# RoboFly.net
KiCad netlist of a schematic drawn in Altium Designer
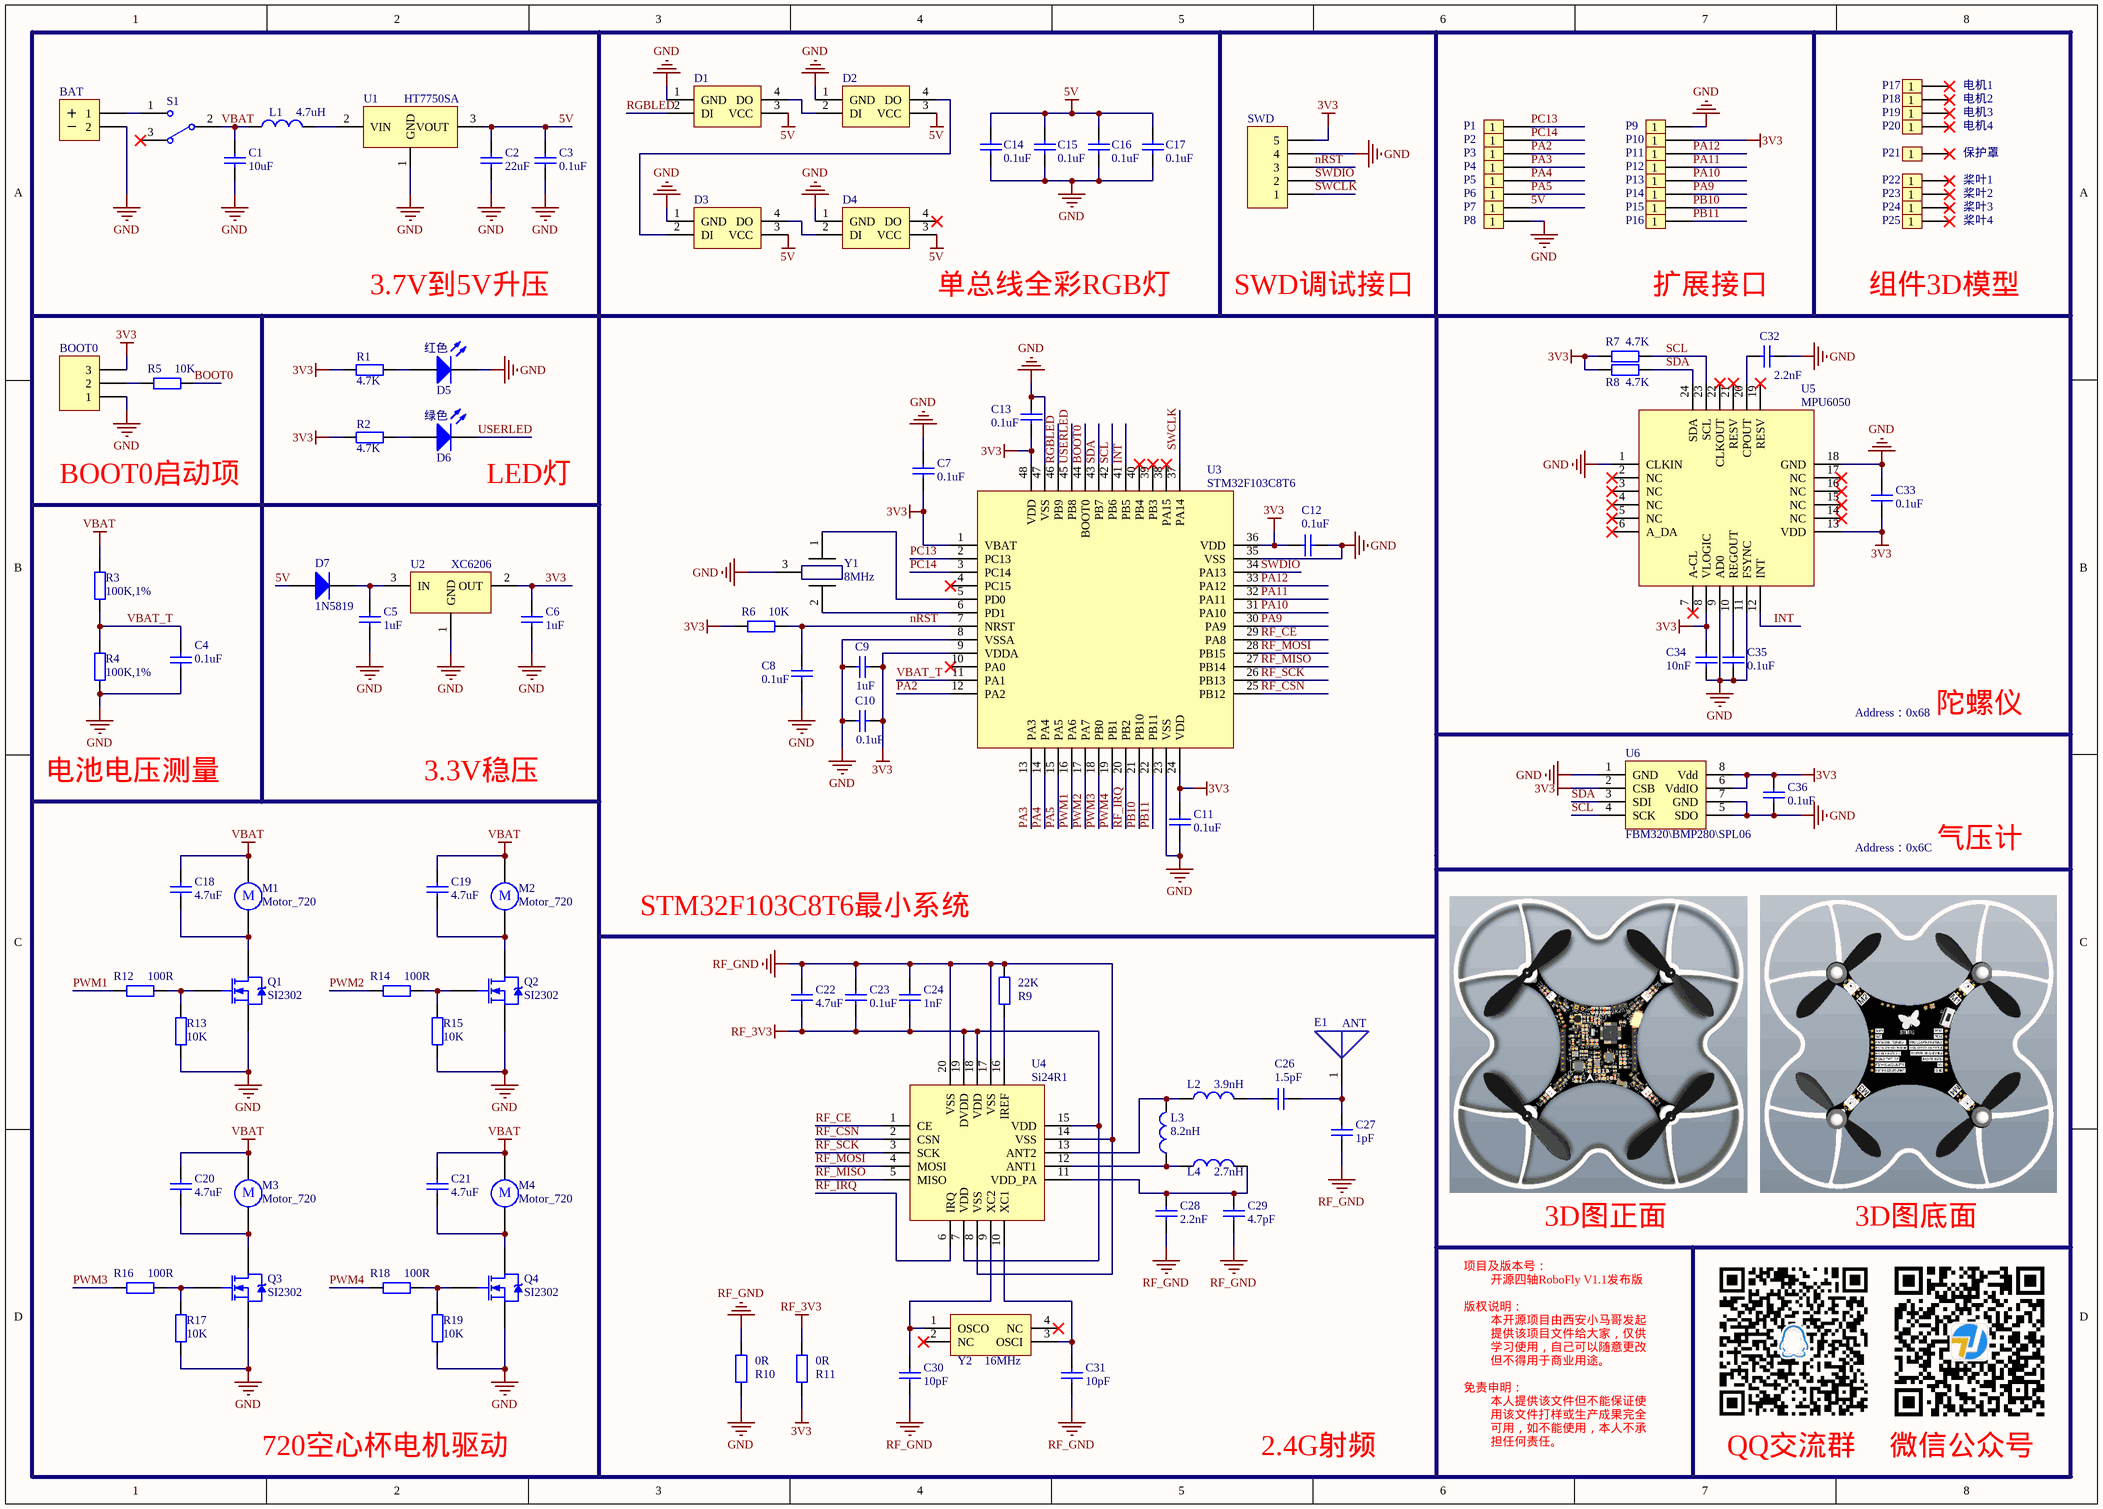
[diagram p0: RoboFly.SchDoc]

(export (version "E")
  (design (tool "Eeschema 10.0.6"))
  (components
    (comp (ref "BAT")
      (value "BAT")
      (footprint "BAT")
      (description "Header, 2-Pin")
      (fields (field (name "PUBLISHER") "mazhongwei"))
      (libsource (lib "RoboFly") (part "BAT"))
    )
    (comp (ref "BOOT0")
      (value "BOOT")
      (footprint "HEADER1X3")
      (description "Header, 3-Pin")
      (fields (field (name "PUBLISHER") "Altium Limited"))
      (libsource (lib "RoboFly") (part "Header 3"))
    )
    (comp (ref "C1")
      (value "10uF")
      (footprint "C_0603")
      (fields (field (name "Comment") "C_0603") (field (name "PUBLISHER") "Altium Limited"))
      (libsource (lib "RoboFly") (part "C_0603"))
    )
    (comp (ref "C2")
      (value "22uF")
      (footprint "C_0603")
      (fields (field (name "Comment") "C_0603") (field (name "PUBLISHER") "Altium Limited"))
      (libsource (lib "RoboFly") (part "C_0603"))
    )
    (comp (ref "C3")
      (value "0.1uF")
      (footprint "C_0603")
      (fields (field (name "Comment") "C_0603") (field (name "PUBLISHER") "Altium Limited"))
      (libsource (lib "RoboFly") (part "C_0603"))
    )
    (comp (ref "C4")
      (value "0.1uF")
      (footprint "C_0603")
      (fields (field (name "Comment") "C_0603") (field (name "PUBLISHER") "Altium Limited"))
      (libsource (lib "RoboFly") (part "C_0603"))
    )
    (comp (ref "C5")
      (value "1uF")
      (footprint "C_0603")
      (fields (field (name "Comment") "C_0603") (field (name "PUBLISHER") "Altium Limited"))
      (libsource (lib "RoboFly") (part "C_0603"))
    )
    (comp (ref "C6")
      (value "1uF")
      (footprint "C_0603")
      (fields (field (name "Comment") "C_0603") (field (name "PUBLISHER") "Altium Limited"))
      (libsource (lib "RoboFly") (part "C_0603"))
    )
    (comp (ref "C7")
      (value "0.1uF")
      (footprint "C_0603")
      (fields (field (name "Comment") "C_0603") (field (name "PUBLISHER") "Altium Limited"))
      (libsource (lib "RoboFly") (part "C_0603"))
    )
    (comp (ref "C8")
      (value "0.1uF")
      (footprint "C_0603")
      (fields (field (name "Comment") "C_0603") (field (name "PUBLISHER") "Altium Limited"))
      (libsource (lib "RoboFly") (part "C_0603"))
    )
    (comp (ref "C9")
      (value "1uF")
      (footprint "C_0603")
      (fields (field (name "Comment") "C_0603") (field (name "PUBLISHER") "Altium Limited"))
      (libsource (lib "RoboFly") (part "C_0603"))
    )
    (comp (ref "C10")
      (value "0.1uF")
      (footprint "C_0603")
      (fields (field (name "Comment") "C_0603") (field (name "PUBLISHER") "Altium Limited"))
      (libsource (lib "RoboFly") (part "C_0603"))
    )
    (comp (ref "C11")
      (value "0.1uF")
      (footprint "C_0603")
      (fields (field (name "Comment") "C_0603") (field (name "PUBLISHER") "Altium Limited"))
      (libsource (lib "RoboFly") (part "C_0603"))
    )
    (comp (ref "C12")
      (value "0.1uF")
      (footprint "C_0603")
      (fields (field (name "Comment") "C_0603") (field (name "PUBLISHER") "Altium Limited"))
      (libsource (lib "RoboFly") (part "C_0603"))
    )
    (comp (ref "C13")
      (value "0.1uF")
      (footprint "C_0603")
      (fields (field (name "Comment") "C_0603") (field (name "PUBLISHER") "Altium Limited"))
      (libsource (lib "RoboFly") (part "C_0603"))
    )
    (comp (ref "C14")
      (value "0.1uF")
      (footprint "C_0603")
      (fields (field (name "Comment") "C_0603") (field (name "PUBLISHER") "Altium Limited"))
      (libsource (lib "RoboFly") (part "C_0603"))
    )
    (comp (ref "C15")
      (value "0.1uF")
      (footprint "C_0603")
      (fields (field (name "Comment") "C_0603") (field (name "PUBLISHER") "Altium Limited"))
      (libsource (lib "RoboFly") (part "C_0603"))
    )
    (comp (ref "C16")
      (value "0.1uF")
      (footprint "C_0603")
      (fields (field (name "Comment") "C_0603") (field (name "PUBLISHER") "Altium Limited"))
      (libsource (lib "RoboFly") (part "C_0603"))
    )
    (comp (ref "C17")
      (value "0.1uF")
      (footprint "C_0603")
      (fields (field (name "Comment") "C_0603") (field (name "PUBLISHER") "Altium Limited"))
      (libsource (lib "RoboFly") (part "C_0603"))
    )
    (comp (ref "C18")
      (value "4.7uF")
      (footprint "C_0603")
      (fields (field (name "Comment") "C_0603") (field (name "PUBLISHER") "Altium Limited"))
      (libsource (lib "RoboFly") (part "C_0603"))
    )
    (comp (ref "C19")
      (value "4.7uF")
      (footprint "C_0603")
      (fields (field (name "Comment") "C_0603") (field (name "PUBLISHER") "Altium Limited"))
      (libsource (lib "RoboFly") (part "C_0603"))
    )
    (comp (ref "C20")
      (value "4.7uF")
      (footprint "C_0603")
      (fields (field (name "Comment") "C_0603") (field (name "PUBLISHER") "Altium Limited"))
      (libsource (lib "RoboFly") (part "C_0603"))
    )
    (comp (ref "C21")
      (value "4.7uF")
      (footprint "C_0603")
      (fields (field (name "Comment") "C_0603") (field (name "PUBLISHER") "Altium Limited"))
      (libsource (lib "RoboFly") (part "C_0603"))
    )
    (comp (ref "C22")
      (value "4.7uF")
      (footprint "C_0603")
      (fields (field (name "Comment") "C_0603") (field (name "PUBLISHER") "Altium Limited"))
      (libsource (lib "RoboFly") (part "C_0603"))
    )
    (comp (ref "C23")
      (value "0.1uF")
      (footprint "C_0603")
      (fields (field (name "Comment") "C_0603") (field (name "PUBLISHER") "Altium Limited"))
      (libsource (lib "RoboFly") (part "C_0603"))
    )
    (comp (ref "C24")
      (value "1nF")
      (footprint "C_0603")
      (fields (field (name "Comment") "C_0603") (field (name "PUBLISHER") "Altium Limited"))
      (libsource (lib "RoboFly") (part "C_0603"))
    )
    (comp (ref "C26")
      (value "1.5pF")
      (footprint "C_0603")
      (fields (field (name "Comment") "C_0603") (field (name "PUBLISHER") "Altium Limited"))
      (libsource (lib "RoboFly") (part "C_0603"))
    )
    (comp (ref "C27")
      (value "1pF")
      (footprint "C_0603")
      (fields (field (name "Comment") "C_0603") (field (name "PUBLISHER") "Altium Limited"))
      (libsource (lib "RoboFly") (part "C_0603"))
    )
    (comp (ref "C28")
      (value "2.2nF")
      (footprint "C_0603")
      (fields (field (name "Comment") "C_0603") (field (name "PUBLISHER") "Altium Limited"))
      (libsource (lib "RoboFly") (part "C_0603"))
    )
    (comp (ref "C29")
      (value "4.7pF")
      (footprint "C_0603")
      (fields (field (name "Comment") "C_0603") (field (name "PUBLISHER") "Altium Limited"))
      (libsource (lib "RoboFly") (part "C_0603"))
    )
    (comp (ref "C30")
      (value "10pF")
      (footprint "C_0603")
      (fields (field (name "Comment") "C_0603") (field (name "PUBLISHER") "Altium Limited"))
      (libsource (lib "RoboFly") (part "C_0603"))
    )
    (comp (ref "C31")
      (value "10pF")
      (footprint "C_0603")
      (fields (field (name "Comment") "C_0603") (field (name "PUBLISHER") "Altium Limited"))
      (libsource (lib "RoboFly") (part "C_0603"))
    )
    (comp (ref "C32")
      (value "2.2nF")
      (footprint "C_0603")
      (fields (field (name "Comment") "C_0603") (field (name "PUBLISHER") "Altium Limited"))
      (libsource (lib "RoboFly") (part "C_0603"))
    )
    (comp (ref "C33")
      (value "0.1uF")
      (footprint "C_0603")
      (fields (field (name "Comment") "C_0603") (field (name "PUBLISHER") "Altium Limited"))
      (libsource (lib "RoboFly") (part "C_0603"))
    )
    (comp (ref "C34")
      (value "10nF")
      (footprint "C_0603")
      (fields (field (name "Comment") "C_0603") (field (name "PUBLISHER") "Altium Limited"))
      (libsource (lib "RoboFly") (part "C_0603"))
    )
    (comp (ref "C35")
      (value "0.1uF")
      (footprint "C_0603")
      (fields (field (name "Comment") "C_0603") (field (name "PUBLISHER") "Altium Limited"))
      (libsource (lib "RoboFly") (part "C_0603"))
    )
    (comp (ref "C36")
      (value "0.1uF")
      (footprint "C_0603")
      (fields (field (name "Comment") "C_0603") (field (name "PUBLISHER") "Altium Limited"))
      (libsource (lib "RoboFly") (part "C_0603"))
    )
    (comp (ref "D1")
      (value "P923D")
      (footprint "RGB_LED_5050")
      (fields (field (name "PUBLISHER") "mazhongwei"))
      (libsource (lib "RoboFly") (part "P923D"))
    )
    (comp (ref "D2")
      (value "P923D")
      (footprint "RGB_LED_5050")
      (fields (field (name "PUBLISHER") "mazhongwei"))
      (libsource (lib "RoboFly") (part "P923D"))
    )
    (comp (ref "D3")
      (value "P923D")
      (footprint "RGB_LED_5050")
      (fields (field (name "PUBLISHER") "mazhongwei"))
      (libsource (lib "RoboFly") (part "P923D"))
    )
    (comp (ref "D4")
      (value "P923D")
      (footprint "RGB_LED_5050")
      (fields (field (name "PUBLISHER") "mazhongwei"))
      (libsource (lib "RoboFly") (part "P923D"))
    )
    (comp (ref "D5")
      (value "红色")
      (footprint "LED-0603")
      (description "发光二极管")
      (fields (field (name "PUBLISHER") "Altium Limited"))
      (libsource (lib "RoboFly") (part "LED 0603"))
    )
    (comp (ref "D6")
      (value "绿色")
      (footprint "LED-0603")
      (description "发光二极管")
      (fields (field (name "PUBLISHER") "Altium Limited"))
      (libsource (lib "RoboFly") (part "LED 0603"))
    )
    (comp (ref "D7")
      (value "1N5819")
      (footprint "SOD-123")
      (description "Default Diode")
      (fields (field (name "PUBLISHER") "mazhongwei"))
      (libsource (lib "RoboFly") (part "Diode"))
    )
    (comp (ref "E1")
      (value "ANT")
      (footprint "ANT")
      (fields (field (name "PUBLISHER") "mazhongwei"))
      (libsource (lib "RoboFly") (part "ANT"))
    )
    (comp (ref "L1")
      (value "4.7uH")
      (footprint "L_1210")
      (description "电感")
      (fields (field (name "Comment") "Inductor") (field (name "PUBLISHER") "Altium Limited"))
      (libsource (lib "RoboFly") (part "Inductor"))
    )
    (comp (ref "L2")
      (value "3.9nH")
      (footprint "L_0603")
      (description "电感")
      (fields (field (name "Comment") "Inductor") (field (name "PUBLISHER") "Altium Limited"))
      (libsource (lib "RoboFly") (part "Inductor_1"))
    )
    (comp (ref "L3")
      (value "8.2nH")
      (footprint "L_0603")
      (description "电感")
      (fields (field (name "Comment") "Inductor") (field (name "PUBLISHER") "Altium Limited"))
      (libsource (lib "RoboFly") (part "Inductor_1"))
    )
    (comp (ref "L4")
      (value "2.7nH")
      (footprint "L_0603")
      (description "电感")
      (fields (field (name "Comment") "Inductor") (field (name "PUBLISHER") "Altium Limited"))
      (libsource (lib "RoboFly") (part "Inductor_1"))
    )
    (comp (ref "M1")
      (value "Motor_720")
      (footprint "MOTOR")
      (description "Motor, General Kind")
      (fields (field (name "PUBLISHER") "mazhongwei"))
      (libsource (lib "RoboFly") (part "Motor_720"))
    )
    (comp (ref "M2")
      (value "Motor_720")
      (footprint "MOTOR")
      (description "Motor, General Kind")
      (fields (field (name "PUBLISHER") "mazhongwei"))
      (libsource (lib "RoboFly") (part "Motor_720"))
    )
    (comp (ref "M3")
      (value "Motor_720")
      (footprint "MOTOR")
      (description "Motor, General Kind")
      (fields (field (name "PUBLISHER") "mazhongwei"))
      (libsource (lib "RoboFly") (part "Motor_720"))
    )
    (comp (ref "M4")
      (value "Motor_720")
      (footprint "MOTOR")
      (description "Motor, General Kind")
      (fields (field (name "PUBLISHER") "mazhongwei"))
      (libsource (lib "RoboFly") (part "Motor_720"))
    )
    (comp (ref "P1")
      (value "Header 1")
      (footprint "HEADER1")
      (fields (field (name "PUBLISHER") "Altium Limited"))
      (libsource (lib "RoboFly") (part "Header 1"))
    )
    (comp (ref "P2")
      (value "Header 1")
      (footprint "HEADER1")
      (fields (field (name "PUBLISHER") "Altium Limited"))
      (libsource (lib "RoboFly") (part "Header 1"))
    )
    (comp (ref "P3")
      (value "Header 1")
      (footprint "HEADER1")
      (fields (field (name "PUBLISHER") "Altium Limited"))
      (libsource (lib "RoboFly") (part "Header 1"))
    )
    (comp (ref "P4")
      (value "Header 1")
      (footprint "HEADER1")
      (fields (field (name "PUBLISHER") "Altium Limited"))
      (libsource (lib "RoboFly") (part "Header 1"))
    )
    (comp (ref "P5")
      (value "Header 1")
      (footprint "HEADER1")
      (fields (field (name "PUBLISHER") "Altium Limited"))
      (libsource (lib "RoboFly") (part "Header 1"))
    )
    (comp (ref "P6")
      (value "Header 1")
      (footprint "HEADER1")
      (fields (field (name "PUBLISHER") "Altium Limited"))
      (libsource (lib "RoboFly") (part "Header 1"))
    )
    (comp (ref "P7")
      (value "Header 1")
      (footprint "HEADER1")
      (fields (field (name "PUBLISHER") "Altium Limited"))
      (libsource (lib "RoboFly") (part "Header 1"))
    )
    (comp (ref "P8")
      (value "Header 1")
      (footprint "HEADER1")
      (fields (field (name "PUBLISHER") "Altium Limited"))
      (libsource (lib "RoboFly") (part "Header 1"))
    )
    (comp (ref "P9")
      (value "Header 1")
      (footprint "HEADER1")
      (fields (field (name "PUBLISHER") "Altium Limited"))
      (libsource (lib "RoboFly") (part "Header 1"))
    )
    (comp (ref "P10")
      (value "Header 1")
      (footprint "HEADER1")
      (fields (field (name "PUBLISHER") "Altium Limited"))
      (libsource (lib "RoboFly") (part "Header 1"))
    )
    (comp (ref "P11")
      (value "Header 1")
      (footprint "HEADER1")
      (fields (field (name "PUBLISHER") "Altium Limited"))
      (libsource (lib "RoboFly") (part "Header 1"))
    )
    (comp (ref "P12")
      (value "Header 1")
      (footprint "HEADER1")
      (fields (field (name "PUBLISHER") "Altium Limited"))
      (libsource (lib "RoboFly") (part "Header 1"))
    )
    (comp (ref "P13")
      (value "Header 1")
      (footprint "HEADER1")
      (fields (field (name "PUBLISHER") "Altium Limited"))
      (libsource (lib "RoboFly") (part "Header 1"))
    )
    (comp (ref "P14")
      (value "Header 1")
      (footprint "HEADER1")
      (fields (field (name "PUBLISHER") "Altium Limited"))
      (libsource (lib "RoboFly") (part "Header 1"))
    )
    (comp (ref "P15")
      (value "Header 1")
      (footprint "HEADER1")
      (fields (field (name "PUBLISHER") "Altium Limited"))
      (libsource (lib "RoboFly") (part "Header 1"))
    )
    (comp (ref "P16")
      (value "Header 1")
      (footprint "HEADER1")
      (fields (field (name "PUBLISHER") "Altium Limited"))
      (libsource (lib "RoboFly") (part "Header 1"))
    )
    (comp (ref "P17")
      (value "Header 1")
      (footprint "720Motor")
      (fields (field (name "PUBLISHER") "Altium Limited"))
      (libsource (lib "RoboFly") (part "Header 1"))
    )
    (comp (ref "P18")
      (value "Header 1")
      (footprint "720Motor")
      (fields (field (name "PUBLISHER") "Altium Limited"))
      (libsource (lib "RoboFly") (part "Header 1"))
    )
    (comp (ref "P19")
      (value "Header 1")
      (footprint "720Motor")
      (fields (field (name "PUBLISHER") "Altium Limited"))
      (libsource (lib "RoboFly") (part "Header 1"))
    )
    (comp (ref "P20")
      (value "Header 1")
      (footprint "720Motor")
      (fields (field (name "PUBLISHER") "Altium Limited"))
      (libsource (lib "RoboFly") (part "Header 1"))
    )
    (comp (ref "P21")
      (value "Header 1")
      (footprint "PROTECT_COVER")
      (fields (field (name "PUBLISHER") "Altium Limited"))
      (libsource (lib "RoboFly") (part "Header 1"))
    )
    (comp (ref "P22")
      (value "Header 1")
      (footprint "BLADEB")
      (fields (field (name "PUBLISHER") "Altium Limited"))
      (libsource (lib "RoboFly") (part "Header 1"))
    )
    (comp (ref "P23")
      (value "Header 1")
      (footprint "BLADEA")
      (fields (field (name "PUBLISHER") "Altium Limited"))
      (libsource (lib "RoboFly") (part "Header 1"))
    )
    (comp (ref "P24")
      (value "Header 1")
      (footprint "BLADEB")
      (fields (field (name "PUBLISHER") "Altium Limited"))
      (libsource (lib "RoboFly") (part "Header 1"))
    )
    (comp (ref "P25")
      (value "Header 1")
      (footprint "BLADEA")
      (fields (field (name "PUBLISHER") "Altium Limited"))
      (libsource (lib "RoboFly") (part "Header 1"))
    )
    (comp (ref "Q1")
      (value "SI2302")
      (footprint "SOT-23(SOT-23-3)")
      (description "N-Channel Power MOSFET")
      (fields (field (name "PUBLISHER") "mazhongwei"))
      (libsource (lib "RoboFly") (part "SI2302"))
    )
    (comp (ref "Q2")
      (value "SI2302")
      (footprint "SOT-23(SOT-23-3)")
      (description "N-Channel Power MOSFET")
      (fields (field (name "PUBLISHER") "mazhongwei"))
      (libsource (lib "RoboFly") (part "SI2302"))
    )
    (comp (ref "Q3")
      (value "SI2302")
      (footprint "SOT-23(SOT-23-3)")
      (description "N-Channel Power MOSFET")
      (fields (field (name "PUBLISHER") "mazhongwei"))
      (libsource (lib "RoboFly") (part "SI2302"))
    )
    (comp (ref "Q4")
      (value "SI2302")
      (footprint "SOT-23(SOT-23-3)")
      (description "N-Channel Power MOSFET")
      (fields (field (name "PUBLISHER") "mazhongwei"))
      (libsource (lib "RoboFly") (part "SI2302"))
    )
    (comp (ref "R1")
      (value "4.7K")
      (footprint "R_0603")
      (fields (field (name "Comment") "R_0603") (field (name "PUBLISHER") "Altium Limited"))
      (libsource (lib "") (part "R_0603_1"))
    )
    (comp (ref "R2")
      (value "4.7K")
      (footprint "R_0603")
      (fields (field (name "Comment") "R_0603") (field (name "PUBLISHER") "Altium Limited"))
      (libsource (lib "") (part "R_0603_1"))
    )
    (comp (ref "R3")
      (value "100K,1%")
      (footprint "R_0603")
      (fields (field (name "Comment") "R_0603") (field (name "PUBLISHER") "Altium Limited"))
      (libsource (lib "RoboFly") (part "R_0603"))
    )
    (comp (ref "R4")
      (value "100K,1%")
      (footprint "R_0603")
      (fields (field (name "Comment") "R_0603") (field (name "PUBLISHER") "Altium Limited"))
      (libsource (lib "RoboFly") (part "R_0603"))
    )
    (comp (ref "R5")
      (value "10K")
      (footprint "R_0603")
      (fields (field (name "Comment") "R_0603") (field (name "PUBLISHER") "Altium Limited"))
      (libsource (lib "") (part "R_0603_1"))
    )
    (comp (ref "R6")
      (value "10K")
      (footprint "R_0603")
      (fields (field (name "Comment") "R_0603") (field (name "PUBLISHER") "Altium Limited"))
      (libsource (lib "") (part "R_0603_2"))
    )
    (comp (ref "R7")
      (value "4.7K")
      (footprint "R_0603")
      (fields (field (name "Comment") "R_0603") (field (name "PUBLISHER") "Altium Limited"))
      (libsource (lib "") (part "R_0603_1"))
    )
    (comp (ref "R8")
      (value "4.7K")
      (footprint "R_0603")
      (fields (field (name "Comment") "R_0603") (field (name "PUBLISHER") "Altium Limited"))
      (libsource (lib "") (part "R_0603_1"))
    )
    (comp (ref "R9")
      (value "22K")
      (footprint "R_0603")
      (fields (field (name "Comment") "R_0603") (field (name "PUBLISHER") "Altium Limited"))
      (libsource (lib "RoboFly") (part "R_0603"))
    )
    (comp (ref "R10")
      (value "0R")
      (footprint "R_0603")
      (fields (field (name "Comment") "R_0603") (field (name "PUBLISHER") "Altium Limited"))
      (libsource (lib "RoboFly") (part "R_0603"))
    )
    (comp (ref "R11")
      (value "0R")
      (footprint "R_0603")
      (fields (field (name "Comment") "R_0603") (field (name "PUBLISHER") "Altium Limited"))
      (libsource (lib "RoboFly") (part "R_0603"))
    )
    (comp (ref "R12")
      (value "100R")
      (footprint "R_0603")
      (fields (field (name "Comment") "R_0603") (field (name "PUBLISHER") "Altium Limited"))
      (libsource (lib "") (part "R_0603_1"))
    )
    (comp (ref "R13")
      (value "10K")
      (footprint "R_0603")
      (fields (field (name "Comment") "R_0603") (field (name "PUBLISHER") "Altium Limited"))
      (libsource (lib "RoboFly") (part "R_0603"))
    )
    (comp (ref "R14")
      (value "100R")
      (footprint "R_0603")
      (fields (field (name "Comment") "R_0603") (field (name "PUBLISHER") "Altium Limited"))
      (libsource (lib "") (part "R_0603_1"))
    )
    (comp (ref "R15")
      (value "10K")
      (footprint "R_0603")
      (fields (field (name "Comment") "R_0603") (field (name "PUBLISHER") "Altium Limited"))
      (libsource (lib "RoboFly") (part "R_0603"))
    )
    (comp (ref "R16")
      (value "100R")
      (footprint "R_0603")
      (fields (field (name "Comment") "R_0603") (field (name "PUBLISHER") "Altium Limited"))
      (libsource (lib "") (part "R_0603_1"))
    )
    (comp (ref "R17")
      (value "10K")
      (footprint "R_0603")
      (fields (field (name "Comment") "R_0603") (field (name "PUBLISHER") "Altium Limited"))
      (libsource (lib "RoboFly") (part "R_0603"))
    )
    (comp (ref "R18")
      (value "100R")
      (footprint "R_0603")
      (fields (field (name "Comment") "R_0603") (field (name "PUBLISHER") "Altium Limited"))
      (libsource (lib "") (part "R_0603_1"))
    )
    (comp (ref "R19")
      (value "10K")
      (footprint "R_0603")
      (fields (field (name "Comment") "R_0603") (field (name "PUBLISHER") "Altium Limited"))
      (libsource (lib "RoboFly") (part "R_0603"))
    )
    (comp (ref "S1")
      (value "SW-SPDT")
      (footprint "SWITCH_PWR")
      (description "SPDT Subminiature Toggle Switch, Right Angle Mounting, Vertical Actuation")
      (fields (field (name "PUBLISHER") "mazhongwei"))
      (libsource (lib "RoboFly") (part "SW-SPDT"))
    )
    (comp (ref "SWD")
      (value "SWD")
      (footprint "SH1_0X5P_WT")
      (description "Header, 5-Pin")
      (fields (field (name "PUBLISHER") "Altium Limited"))
      (libsource (lib "RoboFly") (part "Header 5"))
    )
    (comp (ref "U1")
      (value "HT7750SA")
      (footprint "SOT-23(SOT-23-3)")
      (libsource (lib "RoboFly") (part "HT7750SA"))
    )
    (comp (ref "U2")
      (value "XC6206")
      (footprint "SOT-23(SOT-23-3)")
      (fields (field (name "PUBLISHER") "mazhongwei"))
      (libsource (lib "RoboFly") (part "XC6206"))
    )
    (comp (ref "U3")
      (value "STM32F103C8T6")
      (footprint "LQFP-48_7x7x05P")
      (libsource (lib "RoboFly") (part "STM32F103C8T6"))
    )
    (comp (ref "U4") (value "Si24R1") (footprint "QFN20") (libsource (lib "RoboFly") (part "nRF24L01")))
    (comp (ref "U5")
      (value "MPU6050")
      (footprint "QFN-24_4x4x05P")
      (libsource (lib "RoboFly") (part "MPU6050"))
    )
    (comp (ref "U6")
      (value "FBM32~{0}BMP28~{0}SPL06")
      (footprint "LGA-2_5X2MM")
      (description "气压计")
      (fields (field (name "PUBLISHER") "mazhongwei"))
      (libsource (lib "RoboFly") (part "FBM320"))
    )
    (comp (ref "Y1")
      (value "8MHz")
      (footprint "SMD-cstse800G52-r0")
      (fields (field (name "Comment") "XTAL") (field (name "PUBLISHER") "mazhongwei"))
      (libsource (lib "RoboFly") (part "XTAL_2"))
    )
    (comp (ref "Y2")
      (value "16MHz")
      (footprint "SMD-3225_4P")
      (description "XTAL16M")
      (fields (field (name "Comment") "XTAL"))
      (libsource (lib "RoboFly") (part "XTAL16M"))
    )
  )
  (nets
    (net (code "1") (name "/BOOT0") (class "Default")
      (node (ref "R5") (pin "2") (pinfunction "2_2") (pintype "passive"))
      (node (ref "U3") (pin "44") (pinfunction "BOOT0_44") (pintype "passive"))
    )
    (net (code "2") (name "/INT") (class "Default")
      (node (ref "U3") (pin "41") (pinfunction "PB5_41") (pintype "passive"))
      (node (ref "U5") (pin "12") (pinfunction "INT_12") (pintype "passive"))
    )
    (net (code "3") (name "/PA2") (class "Default")
      (node (ref "P3") (pin "1") (pinfunction "1_1") (pintype "passive"))
      (node (ref "U3") (pin "12") (pinfunction "PA2_12") (pintype "passive"))
    )
    (net (code "4") (name "/PA3") (class "Default")
      (node (ref "P4") (pin "1") (pinfunction "1_1") (pintype "passive"))
      (node (ref "U3") (pin "13") (pinfunction "PA3_13") (pintype "passive"))
    )
    (net (code "5") (name "/PA4") (class "Default")
      (node (ref "P5") (pin "1") (pinfunction "1_1") (pintype "passive"))
      (node (ref "U3") (pin "14") (pinfunction "PA4_14") (pintype "passive"))
    )
    (net (code "6") (name "/PA5") (class "Default")
      (node (ref "P6") (pin "1") (pinfunction "1_1") (pintype "passive"))
      (node (ref "U3") (pin "15") (pinfunction "PA5_15") (pintype "passive"))
    )
    (net (code "7") (name "/PA9") (class "Default")
      (node (ref "P14") (pin "1") (pinfunction "1_1") (pintype "passive"))
      (node (ref "U3") (pin "30") (pinfunction "PA9_30") (pintype "passive"))
    )
    (net (code "8") (name "/PA10") (class "Default")
      (node (ref "P13") (pin "1") (pinfunction "1_1") (pintype "passive"))
      (node (ref "U3") (pin "31") (pinfunction "PA10_31") (pintype "passive"))
    )
    (net (code "9") (name "/PA11") (class "Default")
      (node (ref "P12") (pin "1") (pinfunction "1_1") (pintype "passive"))
      (node (ref "U3") (pin "32") (pinfunction "PA11_32") (pintype "passive"))
    )
    (net (code "10") (name "/PA12") (class "Default")
      (node (ref "P11") (pin "1") (pinfunction "1_1") (pintype "passive"))
      (node (ref "U3") (pin "33") (pinfunction "PA12_33") (pintype "passive"))
    )
    (net (code "11") (name "/PB10") (class "Default")
      (node (ref "P15") (pin "1") (pinfunction "1_1") (pintype "passive"))
      (node (ref "U3") (pin "21") (pinfunction "PB10_21") (pintype "passive"))
    )
    (net (code "12") (name "/PB11") (class "Default")
      (node (ref "P16") (pin "1") (pinfunction "1_1") (pintype "passive"))
      (node (ref "U3") (pin "22") (pinfunction "PB11_22") (pintype "passive"))
    )
    (net (code "13") (name "/PC13") (class "Default")
      (node (ref "P1") (pin "1") (pinfunction "1_1") (pintype "passive"))
      (node (ref "U3") (pin "2") (pinfunction "PC13_2") (pintype "passive"))
    )
    (net (code "14") (name "/PC14") (class "Default")
      (node (ref "P2") (pin "1") (pinfunction "1_1") (pintype "passive"))
      (node (ref "U3") (pin "3") (pinfunction "PC14_3") (pintype "passive"))
    )
    (net (code "15") (name "/PWM1") (class "Default")
      (node (ref "R12") (pin "1") (pinfunction "1_1") (pintype "passive"))
      (node (ref "U3") (pin "16") (pinfunction "PA6_16") (pintype "passive"))
    )
    (net (code "16") (name "/PWM2") (class "Default")
      (node (ref "R14") (pin "1") (pinfunction "1_1") (pintype "passive"))
      (node (ref "U3") (pin "17") (pinfunction "PA7_17") (pintype "passive"))
    )
    (net (code "17") (name "/PWM3") (class "Default")
      (node (ref "R16") (pin "1") (pinfunction "1_1") (pintype "passive"))
      (node (ref "U3") (pin "18") (pinfunction "PB0_18") (pintype "passive"))
    )
    (net (code "18") (name "/PWM4") (class "Default")
      (node (ref "R18") (pin "1") (pinfunction "1_1") (pintype "passive"))
      (node (ref "U3") (pin "19") (pinfunction "PB1_19") (pintype "passive"))
    )
    (net (code "19") (name "/RF_CE") (class "Default")
      (node (ref "U3") (pin "29") (pinfunction "PA8_29") (pintype "passive"))
      (node (ref "U4") (pin "1") (pinfunction "CE_1") (pintype "passive"))
    )
    (net (code "20") (name "/RF_CSN") (class "Default")
      (node (ref "U3") (pin "25") (pinfunction "PB12_25") (pintype "passive"))
      (node (ref "U4") (pin "2") (pinfunction "CSN_2") (pintype "passive"))
    )
    (net (code "21") (name "/RF_IRQ") (class "Default")
      (node (ref "U3") (pin "20") (pinfunction "PB2_20") (pintype "passive"))
      (node (ref "U4") (pin "6") (pinfunction "IRQ_6") (pintype "passive"))
    )
    (net (code "22") (name "/RF_MISO") (class "Default")
      (node (ref "U3") (pin "27") (pinfunction "PB14_27") (pintype "passive"))
      (node (ref "U4") (pin "5") (pinfunction "MISO_5") (pintype "passive"))
    )
    (net (code "23") (name "/RF_MOSI") (class "Default")
      (node (ref "U3") (pin "28") (pinfunction "PB15_28") (pintype "passive"))
      (node (ref "U4") (pin "4") (pinfunction "MOSI_4") (pintype "passive"))
    )
    (net (code "24") (name "/RF_SCK") (class "Default")
      (node (ref "U3") (pin "26") (pinfunction "PB13_26") (pintype "passive"))
      (node (ref "U4") (pin "3") (pinfunction "SCK_3") (pintype "passive"))
    )
    (net (code "25") (name "/RGBLED") (class "Default")
      (node (ref "D1") (pin "2") (pinfunction "DI_2") (pintype "passive"))
      (node (ref "U3") (pin "46") (pinfunction "PB9_46") (pintype "passive"))
    )
    (net (code "26") (name "/SCL") (class "Default")
      (node (ref "R7") (pin "2") (pinfunction "2_2") (pintype "passive"))
      (node (ref "U3") (pin "42") (pinfunction "PB6_42") (pintype "passive"))
      (node (ref "U5") (pin "23") (pinfunction "SCL_23") (pintype "passive"))
      (node (ref "U6") (pin "4") (pinfunction "SCK_4") (pintype "passive"))
    )
    (net (code "27") (name "/SDA") (class "Default")
      (node (ref "R8") (pin "2") (pinfunction "2_2") (pintype "passive"))
      (node (ref "U3") (pin "43") (pinfunction "PB7_43") (pintype "passive"))
      (node (ref "U5") (pin "24") (pinfunction "SDA_24") (pintype "passive"))
      (node (ref "U6") (pin "3") (pinfunction "SDI_3") (pintype "passive"))
    )
    (net (code "28") (name "/SWCLK") (class "Default")
      (node (ref "SWD") (pin "1") (pinfunction "1_1") (pintype "passive"))
      (node (ref "U3") (pin "37") (pinfunction "PA14_37") (pintype "passive"))
    )
    (net (code "29") (name "/SWDIO") (class "Default")
      (node (ref "SWD") (pin "2") (pinfunction "2_2") (pintype "passive"))
      (node (ref "U3") (pin "34") (pinfunction "PA13_34") (pintype "passive"))
    )
    (net (code "30") (name "/USERLED") (class "Default")
      (node (ref "D6") (pin "2") (pinfunction "2_2") (pintype "passive"))
      (node (ref "U3") (pin "45") (pinfunction "PB8_45") (pintype "passive"))
    )
    (net (code "31") (name "/VBAT_T") (class "Default")
      (node (ref "C4") (pin "2") (pinfunction "2_2") (pintype "passive"))
      (node (ref "R3") (pin "1") (pinfunction "1_1") (pintype "passive"))
      (node (ref "R4") (pin "2") (pinfunction "2_2") (pintype "passive"))
      (node (ref "U3") (pin "11") (pinfunction "PA1_11") (pintype "passive"))
    )
    (net (code "32") (name "/nRST") (class "Default")
      (node (ref "C8") (pin "2") (pinfunction "2_2") (pintype "passive"))
      (node (ref "R6") (pin "1") (pinfunction "1_1") (pintype "passive"))
      (node (ref "SWD") (pin "3") (pinfunction "3_3") (pintype "passive"))
      (node (ref "U3") (pin "7") (pinfunction "NRST_7") (pintype "passive"))
    )
    (net (code "33") (name "3V3") (class "Default")
      (node (ref "BOOT0") (pin "3") (pinfunction "3_3") (pintype "passive"))
      (node (ref "C10") (pin "2") (pinfunction "2_2") (pintype "passive"))
      (node (ref "C11") (pin "1") (pinfunction "1_1") (pintype "passive"))
      (node (ref "C12") (pin "2") (pinfunction "2_2") (pintype "passive"))
      (node (ref "C13") (pin "1") (pinfunction "1_1") (pintype "passive"))
      (node (ref "C33") (pin "2") (pinfunction "2_2") (pintype "passive"))
      (node (ref "C34") (pin "2") (pinfunction "2_2") (pintype "passive"))
      (node (ref "C36") (pin "1") (pinfunction "1_1") (pintype "passive"))
      (node (ref "C6") (pin "1") (pinfunction "1_1") (pintype "passive"))
      (node (ref "C7") (pin "2") (pinfunction "2_2") (pintype "passive"))
      (node (ref "C9") (pin "2") (pinfunction "2_2") (pintype "passive"))
      (node (ref "P10") (pin "1") (pinfunction "1_1") (pintype "passive"))
      (node (ref "R1") (pin "1") (pinfunction "1_1") (pintype "passive"))
      (node (ref "R11") (pin "1") (pinfunction "1_1") (pintype "passive"))
      (node (ref "R2") (pin "1") (pinfunction "1_1") (pintype "passive"))
      (node (ref "R6") (pin "2") (pinfunction "2_2") (pintype "passive"))
      (node (ref "R7") (pin "1") (pinfunction "1_1") (pintype "passive"))
      (node (ref "R8") (pin "1") (pinfunction "1_1") (pintype "passive"))
      (node (ref "SWD") (pin "5") (pinfunction "5_5") (pintype "passive"))
      (node (ref "U2") (pin "2") (pinfunction "OUT_2") (pintype "passive"))
      (node (ref "U3") (pin "1") (pinfunction "VBAT_1") (pintype "passive"))
      (node (ref "U3") (pin "24") (pinfunction "VDD_24") (pintype "passive"))
      (node (ref "U3") (pin "36") (pinfunction "VDD_36") (pintype "passive"))
      (node (ref "U3") (pin "48") (pinfunction "VDD_48") (pintype "passive"))
      (node (ref "U3") (pin "9") (pinfunction "VDDA_9") (pintype "passive"))
      (node (ref "U5") (pin "13") (pinfunction "VDD_13") (pintype "passive"))
      (node (ref "U5") (pin "8") (pinfunction "VLOGIC_8") (pintype "passive"))
      (node (ref "U6") (pin "2") (pinfunction "CSB_2") (pintype "passive"))
      (node (ref "U6") (pin "6") (pinfunction "VddIO_6") (pintype "passive"))
      (node (ref "U6") (pin "8") (pinfunction "Vdd_8") (pintype "passive"))
    )
    (net (code "34") (name "5V") (class "Default")
      (node (ref "C14") (pin "2") (pinfunction "2_2") (pintype "passive"))
      (node (ref "C15") (pin "2") (pinfunction "2_2") (pintype "passive"))
      (node (ref "C16") (pin "2") (pinfunction "2_2") (pintype "passive"))
      (node (ref "C17") (pin "2") (pinfunction "2_2") (pintype "passive"))
      (node (ref "C2") (pin "1") (pinfunction "1_1") (pintype "passive"))
      (node (ref "C3") (pin "1") (pinfunction "1_1") (pintype "passive"))
      (node (ref "D1") (pin "3") (pinfunction "VCC_3") (pintype "passive"))
      (node (ref "D2") (pin "3") (pinfunction "VCC_3") (pintype "passive"))
      (node (ref "D3") (pin "3") (pinfunction "VCC_3") (pintype "passive"))
      (node (ref "D4") (pin "3") (pinfunction "VCC_3") (pintype "passive"))
      (node (ref "D7") (pin "1") (pinfunction "A_1") (pintype "passive"))
      (node (ref "P7") (pin "1") (pinfunction "1_1") (pintype "passive"))
      (node (ref "U1") (pin "3") (pinfunction "VOUT_3") (pintype "passive"))
    )
    (net (code "35") (name "GND") (class "Default")
      (node (ref "BAT") (pin "2") (pinfunction "2_2") (pintype "passive"))
      (node (ref "BOOT0") (pin "1") (pinfunction "1_1") (pintype "passive"))
      (node (ref "C1") (pin "2") (pinfunction "2_2") (pintype "passive"))
      (node (ref "C10") (pin "1") (pinfunction "1_1") (pintype "passive"))
      (node (ref "C11") (pin "2") (pinfunction "2_2") (pintype "passive"))
      (node (ref "C12") (pin "1") (pinfunction "1_1") (pintype "passive"))
      (node (ref "C13") (pin "2") (pinfunction "2_2") (pintype "passive"))
      (node (ref "C14") (pin "1") (pinfunction "1_1") (pintype "passive"))
      (node (ref "C15") (pin "1") (pinfunction "1_1") (pintype "passive"))
      (node (ref "C16") (pin "1") (pinfunction "1_1") (pintype "passive"))
      (node (ref "C17") (pin "1") (pinfunction "1_1") (pintype "passive"))
      (node (ref "C2") (pin "2") (pinfunction "2_2") (pintype "passive"))
      (node (ref "C3") (pin "2") (pinfunction "2_2") (pintype "passive"))
      (node (ref "C32") (pin "1") (pinfunction "1_1") (pintype "passive"))
      (node (ref "C33") (pin "1") (pinfunction "1_1") (pintype "passive"))
      (node (ref "C34") (pin "1") (pinfunction "1_1") (pintype "passive"))
      (node (ref "C35") (pin "2") (pinfunction "2_2") (pintype "passive"))
      (node (ref "C36") (pin "2") (pinfunction "2_2") (pintype "passive"))
      (node (ref "C4") (pin "1") (pinfunction "1_1") (pintype "passive"))
      (node (ref "C5") (pin "2") (pinfunction "2_2") (pintype "passive"))
      (node (ref "C6") (pin "2") (pinfunction "2_2") (pintype "passive"))
      (node (ref "C7") (pin "1") (pinfunction "1_1") (pintype "passive"))
      (node (ref "C8") (pin "1") (pinfunction "1_1") (pintype "passive"))
      (node (ref "C9") (pin "1") (pinfunction "1_1") (pintype "passive"))
      (node (ref "D1") (pin "1") (pinfunction "GND_1") (pintype "passive"))
      (node (ref "D2") (pin "1") (pinfunction "GND_1") (pintype "passive"))
      (node (ref "D3") (pin "1") (pinfunction "GND_1") (pintype "passive"))
      (node (ref "D4") (pin "1") (pinfunction "GND_1") (pintype "passive"))
      (node (ref "D5") (pin "2") (pinfunction "2_2") (pintype "passive"))
      (node (ref "P8") (pin "1") (pinfunction "1_1") (pintype "passive"))
      (node (ref "P9") (pin "1") (pinfunction "1_1") (pintype "passive"))
      (node (ref "Q1") (pin "2") (pinfunction "S_2") (pintype "passive"))
      (node (ref "Q2") (pin "2") (pinfunction "S_2") (pintype "passive"))
      (node (ref "Q3") (pin "2") (pinfunction "S_2") (pintype "passive"))
      (node (ref "Q4") (pin "2") (pinfunction "S_2") (pintype "passive"))
      (node (ref "R10") (pin "1") (pinfunction "1_1") (pintype "passive"))
      (node (ref "R13") (pin "1") (pinfunction "1_1") (pintype "passive"))
      (node (ref "R15") (pin "1") (pinfunction "1_1") (pintype "passive"))
      (node (ref "R17") (pin "1") (pinfunction "1_1") (pintype "passive"))
      (node (ref "R19") (pin "1") (pinfunction "1_1") (pintype "passive"))
      (node (ref "R4") (pin "1") (pinfunction "1_1") (pintype "passive"))
      (node (ref "SWD") (pin "4") (pinfunction "4_4") (pintype "passive"))
      (node (ref "U1") (pin "1") (pinfunction "GND_1") (pintype "passive"))
      (node (ref "U2") (pin "1") (pinfunction "GND_1") (pintype "passive"))
      (node (ref "U3") (pin "23") (pinfunction "VSS_23") (pintype "passive"))
      (node (ref "U3") (pin "35") (pinfunction "VSS_35") (pintype "passive"))
      (node (ref "U3") (pin "47") (pinfunction "VSS_47") (pintype "passive"))
      (node (ref "U3") (pin "8") (pinfunction "VSSA_8") (pintype "passive"))
      (node (ref "U5") (pin "1") (pinfunction "CLKIN_1") (pintype "passive"))
      (node (ref "U5") (pin "11") (pinfunction "FSYNC_11") (pintype "passive"))
      (node (ref "U5") (pin "18") (pinfunction "GND_18") (pintype "passive"))
      (node (ref "U5") (pin "9") (pinfunction "AD0_9") (pintype "passive"))
      (node (ref "U6") (pin "1") (pinfunction "GND_1") (pintype "passive"))
      (node (ref "U6") (pin "5") (pinfunction "SDO_5") (pintype "passive"))
      (node (ref "U6") (pin "7") (pinfunction "GND_7") (pintype "passive"))
      (node (ref "Y1") (pin "3") (pinfunction "3_3") (pintype "passive"))
    )
    (net (code "36") (name "Net-(BAT-Pad1)") (class "Default")
      (node (ref "BAT") (pin "1") (pinfunction "1_1") (pintype "passive"))
      (node (ref "S1") (pin "1") (pinfunction "1_1") (pintype "passive"))
    )
    (net (code "37") (name "Net-(BOOT0-Pad2)") (class "Default")
      (node (ref "BOOT0") (pin "2") (pinfunction "2_2") (pintype "passive"))
      (node (ref "R5") (pin "1") (pinfunction "1_1") (pintype "passive"))
    )
    (net (code "38") (name "Net-(C26-Pad1)") (class "Default")
      (node (ref "C26") (pin "1") (pinfunction "1_1") (pintype "passive"))
      (node (ref "L2") (pin "2") (pinfunction "2_2") (pintype "passive"))
    )
    (net (code "39") (name "Net-(C26-Pad2)") (class "Default")
      (node (ref "C26") (pin "2") (pinfunction "2_2") (pintype "passive"))
      (node (ref "C27") (pin "2") (pinfunction "2_2") (pintype "passive"))
      (node (ref "E1") (pin "1") (pinfunction "1_1") (pintype "passive"))
    )
    (net (code "40") (name "Net-(D1-DO)") (class "Default")
      (node (ref "D1") (pin "4") (pinfunction "DO_4") (pintype "passive"))
      (node (ref "D2") (pin "2") (pinfunction "DI_2") (pintype "passive"))
    )
    (net (code "41") (name "Net-(D2-DO)") (class "Default")
      (node (ref "D2") (pin "4") (pinfunction "DO_4") (pintype "passive"))
      (node (ref "D3") (pin "2") (pinfunction "DI_2") (pintype "passive"))
    )
    (net (code "42") (name "Net-(D3-DO)") (class "Default")
      (node (ref "D3") (pin "4") (pinfunction "DO_4") (pintype "passive"))
      (node (ref "D4") (pin "2") (pinfunction "DI_2") (pintype "passive"))
    )
    (net (code "43") (name "Net-(D5-Pad1)") (class "Default")
      (node (ref "D5") (pin "1") (pinfunction "1_1") (pintype "passive"))
      (node (ref "R1") (pin "2") (pinfunction "2_2") (pintype "passive"))
    )
    (net (code "44") (name "Net-(D6-Pad1)") (class "Default")
      (node (ref "D6") (pin "1") (pinfunction "1_1") (pintype "passive"))
      (node (ref "R2") (pin "2") (pinfunction "2_2") (pintype "passive"))
    )
    (net (code "45") (name "Net-(D7-K)") (class "Default")
      (node (ref "C5") (pin "1") (pinfunction "1_1") (pintype "passive"))
      (node (ref "D7") (pin "2") (pinfunction "K_2") (pintype "passive"))
      (node (ref "U2") (pin "3") (pinfunction "IN_3") (pintype "passive"))
    )
    (net (code "46") (name "Net-(Q1-D)") (class "Default")
      (node (ref "C18") (pin "1") (pinfunction "1_1") (pintype "passive"))
      (node (ref "M1") (pin "2") (pinfunction "2_2") (pintype "passive"))
      (node (ref "Q1") (pin "3") (pinfunction "D_3") (pintype "passive"))
    )
    (net (code "47") (name "Net-(Q1-G)") (class "Default")
      (node (ref "Q1") (pin "1") (pinfunction "G_1") (pintype "passive"))
      (node (ref "R12") (pin "2") (pinfunction "2_2") (pintype "passive"))
      (node (ref "R13") (pin "2") (pinfunction "2_2") (pintype "passive"))
    )
    (net (code "48") (name "Net-(Q2-D)") (class "Default")
      (node (ref "C19") (pin "1") (pinfunction "1_1") (pintype "passive"))
      (node (ref "M2") (pin "2") (pinfunction "2_2") (pintype "passive"))
      (node (ref "Q2") (pin "3") (pinfunction "D_3") (pintype "passive"))
    )
    (net (code "49") (name "Net-(Q2-G)") (class "Default")
      (node (ref "Q2") (pin "1") (pinfunction "G_1") (pintype "passive"))
      (node (ref "R14") (pin "2") (pinfunction "2_2") (pintype "passive"))
      (node (ref "R15") (pin "2") (pinfunction "2_2") (pintype "passive"))
    )
    (net (code "50") (name "Net-(Q3-D)") (class "Default")
      (node (ref "C20") (pin "1") (pinfunction "1_1") (pintype "passive"))
      (node (ref "M3") (pin "2") (pinfunction "2_2") (pintype "passive"))
      (node (ref "Q3") (pin "3") (pinfunction "D_3") (pintype "passive"))
    )
    (net (code "51") (name "Net-(Q3-G)") (class "Default")
      (node (ref "Q3") (pin "1") (pinfunction "G_1") (pintype "passive"))
      (node (ref "R16") (pin "2") (pinfunction "2_2") (pintype "passive"))
      (node (ref "R17") (pin "2") (pinfunction "2_2") (pintype "passive"))
    )
    (net (code "52") (name "Net-(Q4-D)") (class "Default")
      (node (ref "C21") (pin "1") (pinfunction "1_1") (pintype "passive"))
      (node (ref "M4") (pin "2") (pinfunction "2_2") (pintype "passive"))
      (node (ref "Q4") (pin "3") (pinfunction "D_3") (pintype "passive"))
    )
    (net (code "53") (name "Net-(Q4-G)") (class "Default")
      (node (ref "Q4") (pin "1") (pinfunction "G_1") (pintype "passive"))
      (node (ref "R18") (pin "2") (pinfunction "2_2") (pintype "passive"))
      (node (ref "R19") (pin "2") (pinfunction "2_2") (pintype "passive"))
    )
    (net (code "54") (name "Net-(U1-VIN)") (class "Default")
      (node (ref "L1") (pin "2") (pinfunction "2_2") (pintype "passive"))
      (node (ref "U1") (pin "2") (pinfunction "VIN_2") (pintype "passive"))
    )
    (net (code "55") (name "Net-(U3-PD0)") (class "Default")
      (node (ref "U3") (pin "5") (pinfunction "PD0_5") (pintype "passive"))
      (node (ref "Y1") (pin "1") (pinfunction "1_1") (pintype "passive"))
    )
    (net (code "56") (name "Net-(U3-PD1)") (class "Default")
      (node (ref "U3") (pin "6") (pinfunction "PD1_6") (pintype "passive"))
      (node (ref "Y1") (pin "2") (pinfunction "2_2") (pintype "passive"))
    )
    (net (code "57") (name "Net-(U4-ANT1)") (class "Default")
      (node (ref "L3") (pin "1") (pinfunction "1_1") (pintype "passive"))
      (node (ref "L4") (pin "1") (pinfunction "1_1") (pintype "passive"))
      (node (ref "U4") (pin "12") (pinfunction "ANT1_12") (pintype "passive"))
    )
    (net (code "58") (name "Net-(U4-ANT2)") (class "Default")
      (node (ref "L2") (pin "1") (pinfunction "1_1") (pintype "passive"))
      (node (ref "L3") (pin "2") (pinfunction "2_2") (pintype "passive"))
      (node (ref "U4") (pin "13") (pinfunction "ANT2_13") (pintype "passive"))
    )
    (net (code "59") (name "Net-(U4-IREF)") (class "Default")
      (node (ref "R9") (pin "1") (pinfunction "1_1") (pintype "passive"))
      (node (ref "U4") (pin "16") (pinfunction "IREF_16") (pintype "passive"))
    )
    (net (code "60") (name "Net-(U4-VDD_PA)") (class "Default")
      (node (ref "C28") (pin "2") (pinfunction "2_2") (pintype "passive"))
      (node (ref "C29") (pin "2") (pinfunction "2_2") (pintype "passive"))
      (node (ref "L4") (pin "2") (pinfunction "2_2") (pintype "passive"))
      (node (ref "U4") (pin "11") (pinfunction "VDD_PA_11") (pintype "passive"))
    )
    (net (code "61") (name "Net-(U4-XC1)") (class "Default")
      (node (ref "C31") (pin "2") (pinfunction "2_2") (pintype "passive"))
      (node (ref "U4") (pin "10") (pinfunction "XC1_10") (pintype "passive"))
      (node (ref "Y2") (pin "3") (pinfunction "OSCI_3") (pintype "passive"))
    )
    (net (code "62") (name "Net-(U4-XC2)") (class "Default")
      (node (ref "C30") (pin "2") (pinfunction "2_2") (pintype "passive"))
      (node (ref "U4") (pin "9") (pinfunction "XC2_9") (pintype "passive"))
      (node (ref "Y2") (pin "1") (pinfunction "OSCO_1") (pintype "passive"))
    )
    (net (code "63") (name "Net-(U5-CPOUT)") (class "Default")
      (node (ref "C32") (pin "2") (pinfunction "2_2") (pintype "passive"))
      (node (ref "U5") (pin "20") (pinfunction "CPOUT_20") (pintype "passive"))
    )
    (net (code "64") (name "Net-(U5-REGOUT)") (class "Default")
      (node (ref "C35") (pin "1") (pinfunction "1_1") (pintype "passive"))
      (node (ref "U5") (pin "10") (pinfunction "REGOUT_10") (pintype "passive"))
    )
    (net (code "65") (name "RF_3V3") (class "Default")
      (node (ref "C22") (pin "1") (pinfunction "1_1") (pintype "passive"))
      (node (ref "C23") (pin "1") (pinfunction "1_1") (pintype "passive"))
      (node (ref "C24") (pin "1") (pinfunction "1_1") (pintype "passive"))
      (node (ref "R11") (pin "2") (pinfunction "2_2") (pintype "passive"))
      (node (ref "U4") (pin "15") (pinfunction "VDD_15") (pintype "passive"))
      (node (ref "U4") (pin "18") (pinfunction "VDD_18") (pintype "passive"))
      (node (ref "U4") (pin "19") (pinfunction "DVDD_19") (pintype "passive"))
      (node (ref "U4") (pin "7") (pinfunction "VDD_7") (pintype "passive"))
    )
    (net (code "66") (name "RF_GND") (class "Default")
      (node (ref "C22") (pin "2") (pinfunction "2_2") (pintype "passive"))
      (node (ref "C23") (pin "2") (pinfunction "2_2") (pintype "passive"))
      (node (ref "C24") (pin "2") (pinfunction "2_2") (pintype "passive"))
      (node (ref "C27") (pin "1") (pinfunction "1_1") (pintype "passive"))
      (node (ref "C28") (pin "1") (pinfunction "1_1") (pintype "passive"))
      (node (ref "C29") (pin "1") (pinfunction "1_1") (pintype "passive"))
      (node (ref "C30") (pin "1") (pinfunction "1_1") (pintype "passive"))
      (node (ref "C31") (pin "1") (pinfunction "1_1") (pintype "passive"))
      (node (ref "R10") (pin "2") (pinfunction "2_2") (pintype "passive"))
      (node (ref "R9") (pin "2") (pinfunction "2_2") (pintype "passive"))
      (node (ref "U4") (pin "14") (pinfunction "VSS_14") (pintype "passive"))
      (node (ref "U4") (pin "17") (pinfunction "VSS_17") (pintype "passive"))
      (node (ref "U4") (pin "20") (pinfunction "VSS_20") (pintype "passive"))
      (node (ref "U4") (pin "8") (pinfunction "VSS_8") (pintype "passive"))
    )
    (net (code "67") (name "VBAT") (class "Default")
      (node (ref "C1") (pin "1") (pinfunction "1_1") (pintype "passive"))
      (node (ref "C18") (pin "2") (pinfunction "2_2") (pintype "passive"))
      (node (ref "C19") (pin "2") (pinfunction "2_2") (pintype "passive"))
      (node (ref "C20") (pin "2") (pinfunction "2_2") (pintype "passive"))
      (node (ref "C21") (pin "2") (pinfunction "2_2") (pintype "passive"))
      (node (ref "L1") (pin "1") (pinfunction "1_1") (pintype "passive"))
      (node (ref "M1") (pin "1") (pinfunction "1_1") (pintype "passive"))
      (node (ref "M2") (pin "1") (pinfunction "1_1") (pintype "passive"))
      (node (ref "M3") (pin "1") (pinfunction "1_1") (pintype "passive"))
      (node (ref "M4") (pin "1") (pinfunction "1_1") (pintype "passive"))
      (node (ref "R3") (pin "2") (pinfunction "2_2") (pintype "passive"))
      (node (ref "S1") (pin "2") (pinfunction "2_2") (pintype "passive"))
    )
    (net (code "68") (name "unconnected-(D4-DO-Pad4)") (class "Default")
      (node (ref "D4") (pin "4") (pinfunction "DO_4") (pintype "passive+no_connect"))
    )
    (net (code "69") (name "unconnected-(P17-Pad1)") (class "Default")
      (node (ref "P17") (pin "1") (pinfunction "1_1") (pintype "passive+no_connect"))
    )
    (net (code "70") (name "unconnected-(P18-Pad1)") (class "Default")
      (node (ref "P18") (pin "1") (pinfunction "1_1") (pintype "passive+no_connect"))
    )
    (net (code "71") (name "unconnected-(P19-Pad1)") (class "Default")
      (node (ref "P19") (pin "1") (pinfunction "1_1") (pintype "passive+no_connect"))
    )
    (net (code "72") (name "unconnected-(P20-Pad1)") (class "Default")
      (node (ref "P20") (pin "1") (pinfunction "1_1") (pintype "passive+no_connect"))
    )
    (net (code "73") (name "unconnected-(P21-Pad1)") (class "Default")
      (node (ref "P21") (pin "1") (pinfunction "1_1") (pintype "passive+no_connect"))
    )
    (net (code "74") (name "unconnected-(P22-Pad1)") (class "Default")
      (node (ref "P22") (pin "1") (pinfunction "1_1") (pintype "passive+no_connect"))
    )
    (net (code "75") (name "unconnected-(P23-Pad1)") (class "Default")
      (node (ref "P23") (pin "1") (pinfunction "1_1") (pintype "passive+no_connect"))
    )
    (net (code "76") (name "unconnected-(P24-Pad1)") (class "Default")
      (node (ref "P24") (pin "1") (pinfunction "1_1") (pintype "passive+no_connect"))
    )
    (net (code "77") (name "unconnected-(P25-Pad1)") (class "Default")
      (node (ref "P25") (pin "1") (pinfunction "1_1") (pintype "passive+no_connect"))
    )
    (net (code "78") (name "unconnected-(S1-Pad3)") (class "Default")
      (node (ref "S1") (pin "3") (pinfunction "3_3") (pintype "passive+no_connect"))
    )
    (net (code "79") (name "unconnected-(U3-PA0-Pad10)") (class "Default")
      (node (ref "U3") (pin "10") (pinfunction "PA0_10") (pintype "passive+no_connect"))
    )
    (net (code "80") (name "unconnected-(U3-PA15-Pad38)") (class "Default")
      (node (ref "U3") (pin "38") (pinfunction "PA15_38") (pintype "passive+no_connect"))
    )
    (net (code "81") (name "unconnected-(U3-PB3-Pad39)") (class "Default")
      (node (ref "U3") (pin "39") (pinfunction "PB3_39") (pintype "passive+no_connect"))
    )
    (net (code "82") (name "unconnected-(U3-PB4-Pad40)") (class "Default")
      (node (ref "U3") (pin "40") (pinfunction "PB4_40") (pintype "passive+no_connect"))
    )
    (net (code "83") (name "unconnected-(U3-PC15-Pad4)") (class "Default")
      (node (ref "U3") (pin "4") (pinfunction "PC15_4") (pintype "passive+no_connect"))
    )
    (net (code "84") (name "unconnected-(U5-A-CL-Pad7)") (class "Default")
      (node (ref "U5") (pin "7") (pinfunction "A-CL_7") (pintype "passive+no_connect"))
    )
    (net (code "85") (name "unconnected-(U5-A_DA-Pad6)") (class "Default")
      (node (ref "U5") (pin "6") (pinfunction "A_DA_6") (pintype "passive+no_connect"))
    )
    (net (code "86") (name "unconnected-(U5-CLKOUT-Pad22)") (class "Default")
      (node (ref "U5") (pin "22") (pinfunction "CLKOUT_22") (pintype "passive+no_connect"))
    )
    (net (code "87") (name "unconnected-(U5-NC-Pad2)") (class "Default")
      (node (ref "U5") (pin "2") (pinfunction "NC_2") (pintype "passive+no_connect"))
    )
    (net (code "88") (name "unconnected-(U5-NC-Pad3)") (class "Default")
      (node (ref "U5") (pin "3") (pinfunction "NC_3") (pintype "passive+no_connect"))
    )
    (net (code "89") (name "unconnected-(U5-NC-Pad4)") (class "Default")
      (node (ref "U5") (pin "4") (pinfunction "NC_4") (pintype "passive+no_connect"))
    )
    (net (code "90") (name "unconnected-(U5-NC-Pad5)") (class "Default")
      (node (ref "U5") (pin "5") (pinfunction "NC_5") (pintype "passive+no_connect"))
    )
    (net (code "91") (name "unconnected-(U5-NC-Pad14)") (class "Default")
      (node (ref "U5") (pin "14") (pinfunction "NC_14") (pintype "passive+no_connect"))
    )
    (net (code "92") (name "unconnected-(U5-NC-Pad15)") (class "Default")
      (node (ref "U5") (pin "15") (pinfunction "NC_15") (pintype "passive+no_connect"))
    )
    (net (code "93") (name "unconnected-(U5-NC-Pad16)") (class "Default")
      (node (ref "U5") (pin "16") (pinfunction "NC_16") (pintype "passive+no_connect"))
    )
    (net (code "94") (name "unconnected-(U5-NC-Pad17)") (class "Default")
      (node (ref "U5") (pin "17") (pinfunction "NC_17") (pintype "passive+no_connect"))
    )
    (net (code "95") (name "unconnected-(U5-RESV-Pad19)") (class "Default")
      (node (ref "U5") (pin "19") (pinfunction "RESV_19") (pintype "passive+no_connect"))
    )
    (net (code "96") (name "unconnected-(U5-RESV-Pad21)") (class "Default")
      (node (ref "U5") (pin "21") (pinfunction "RESV_21") (pintype "passive+no_connect"))
    )
    (net (code "97") (name "unconnected-(Y2-NC-Pad2)") (class "Default")
      (node (ref "Y2") (pin "2") (pinfunction "NC_2") (pintype "passive+no_connect"))
    )
    (net (code "98") (name "unconnected-(Y2-NC-Pad4)") (class "Default")
      (node (ref "Y2") (pin "4") (pinfunction "NC_4") (pintype "passive+no_connect"))
    )
  )
)
